# Boost_5V.net
KiCad netlist of a schematic drawn in Altium Designer
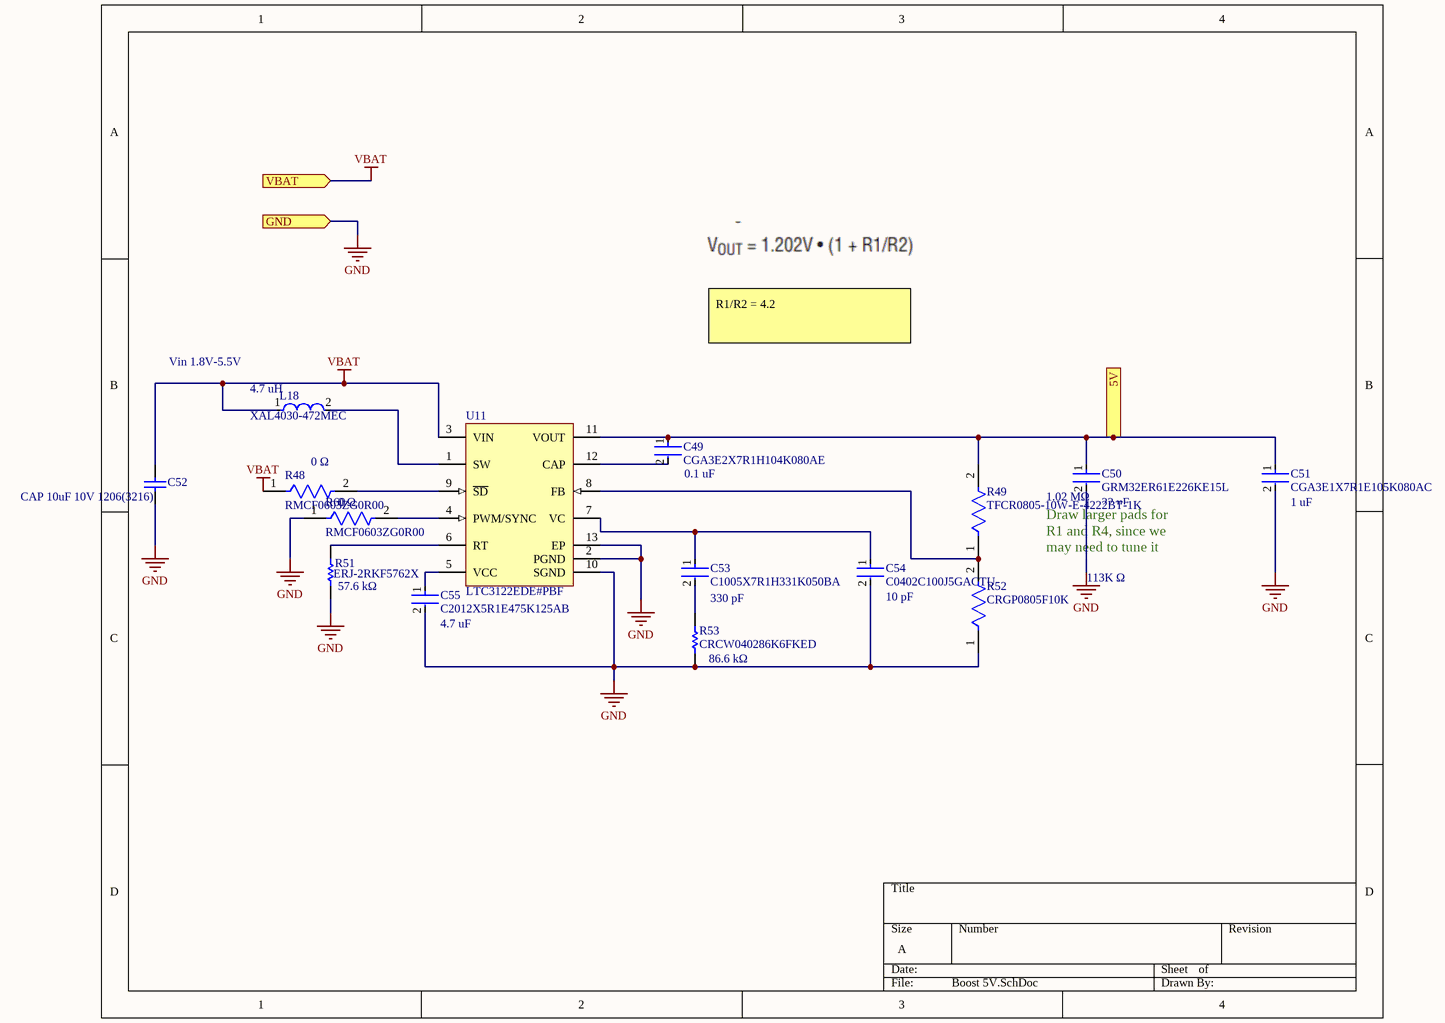
[diagram p0: Boost 5V.SchDoc]

(export (version "E")
  (design (tool "Eeschema 10.0.6"))
  (components
    (comp (ref "C49")
      (value "CGA3E2X7R1H104K080AE")
      (footprint "FP-CGA3E-0_3-0_1-IPC_A")
      (description "Cap Ceramic 100nF 50V X7R 10% Pad SMD 0603 +125°C Automotive T/R")
      (fields (field (name "TOLERANCE") "10%"))
      (libsource (lib "Altium Content Vault") (part "b4654b650e69147ec39a6b967a45e02"))
    )
    (comp (ref "C50")
      (value "GRM32ER61E226KE15L")
      (footprint "FP-GRM32-MFG")
      (description "CAP CER 22UF 25V X5R 1210")
      (fields
        (field (name "TOLERANCE") "10%")
        (field (name "MANUFACTURER") "Murata Electronics North America")
      )
      (libsource (lib "Altium Content Vault") (part "11868f565c42a9108669ba33697ecf6"))
    )
    (comp (ref "C51")
      (value "CGA3E1X7R1E105K080AC")
      (footprint "FP-CGA3E-0_3-0_1-IPC_A")
      (description "Cap Ceramic 1uF 25V X7R 10% Pad SMD 0603 +125°C Automotive T/R")
      (fields (field (name "VOLTAGE") "25V") (field (name "TOLERANCE") "10%"))
      (libsource (lib "Altium Content Vault") (part "b4654b650e69147ec39a6b967a45e02"))
    )
    (comp (ref "C52")
      (value "CAP 10uF 10V 1206(3216)")
      (footprint "CAPC1206(3216)190_L")
      (description "CAP 10uF 10V ±10% 1206 (3216 Metric) Thickness 1.9mm SMD")
      (fields (field (name "TOLERANCE") "Â±10%"))
      (libsource (lib "Altium Content Vault") (part "CAP"))
    )
    (comp (ref "C53")
      (value "C1005X7R1H331K050BA")
      (footprint "FP-C1005-050-0_05-IPC_B")
      (description "Multilayer Ceramic Capacitors 330pF ±10% 50V X7R SMD 0402")
      (fields (field (name "TOLERANCE") "10%"))
      (libsource (lib "Altium Content Vault") (part "b4654b650e69147ec39a6b967a45e02"))
    )
    (comp (ref "C54")
      (value "C0402C100J5GACTU")
      (footprint "FP-C0402-BB-MFG")
      (fields
        (field (name "MANUFACTURER") "Kemet")
        (field (name "OCTOPART") "https://octopart.com/c0402c100j5gactu-kemet-108448")
        (field (name "TOLERANCE") "0.05")
      )
      (libsource (lib "Altium Content Vault") (part "b4654b650e69147ec39a6b967a45e02"))
    )
    (comp (ref "C55")
      (value "C2012X5R1E475K125AB")
      (footprint "FP-C2012-125-0_2-MFG")
      (description "Multilayer Ceramic Capacitors 4.7μF ±10% 25V X5R SMD 0805")
      (fields (field (name "VOLTAGE") "25V") (field (name "TOLERANCE") "10%"))
      (libsource (lib "Altium Content Vault") (part "b4654b650e69147ec39a6b967a45e02"))
    )
    (comp (ref "L18")
      (value "XAL4030-472MEC")
      (footprint "FP-XAL4030-472MEC-MFG")
      (description "Power Inductor (SMD), 4.7 µH, 5.1 A, Shielded, 4.5 A, XAL40xx Series, 4mm x 4mm x 3.1mm")
      (fields (field (name "TOLERANCE") "20%"))
      (libsource (lib "Altium Content Vault") (part "725321dda6339637d4d059423bc1c3c"))
    )
    (comp (ref "R48")
      (value "RMCF0603ZG0R00")
      (footprint "FP-RMCF0603-IPC_B")
      (description "0Ω ±0 0.1W 0603 Thick Film Chip Resistor AEC-Q200 compliant")
      (libsource (lib "Altium Content Vault") (part "1029c3af85768c4190bb7ad29bc67b5"))
    )
    (comp (ref "R49")
      (value "TFCR0805-10W-E-4222BT-1K")
      (footprint "FP-TFCR0805-IPC_A")
      (description "RES Thin Film,  42.2kΩ, 0.1%, 0.1W, 25ppm/°C, 0805")
      (libsource (lib "Altium Content Vault") (part "1029c3af85768c4190bb7ad29bc67b5"))
    )
    (comp (ref "R51")
      (value "ERJ-2RKF5762X")
      (footprint "RESC1005X40X25NL05T05")
      (fields (field (name "MANUFACTURER") "Panasonic"))
      (libsource (lib "Altium Content Vault") (part "RES"))
    )
    (comp (ref "R52")
      (value "CRGP0805F10K")
      (footprint "FP-CRGP0805-IPC_C")
      (description "CRGP 0805 10K 1%")
      (fields
        (field (name "MANUFACTURER") "TE")
        (field (name "OCTOPART") "https://octopart.com/crgp0805f10k-te+connectivity-91018782")
      )
      (libsource (lib "Altium Content Vault") (part "1029c3af85768c4190bb7ad29bc67b5"))
    )
    (comp (ref "R53")
      (value "CRCW040286K6FKED")
      (footprint "RESC1005X40X25NL05T05")
      (fields (field (name "MANUFACTURER") "Vishay Dale"))
      (libsource (lib "Altium Content Vault") (part "RES"))
    )
    (comp (ref "R60")
      (value "RMCF0603ZG0R00")
      (footprint "FP-RMCF0603-IPC_B")
      (description "0Ω ±0 0.1W 0603 Thick Film Chip Resistor AEC-Q200 compliant")
      (libsource (lib "Altium Content Vault") (part "1029c3af85768c4190bb7ad29bc67b5"))
    )
    (comp (ref "U11")
      (value "LTC3122EDE#PBF")
      (footprint "LT-DE-UE-12_V")
      (fields (field (name "MANUFACTURER") "Linear Technology"))
      (libsource (lib "Altium Content Vault") (part "LT-LTC3122-X-12"))
    )
  )
  (nets
    (net (code "1") (name "/5V") (class "Default")
      (node (ref "C49") (pin "1") (pinfunction "1_1") (pintype "passive"))
      (node (ref "C50") (pin "1") (pinfunction "1_1") (pintype "passive"))
      (node (ref "C51") (pin "1") (pinfunction "1_1") (pintype "passive"))
      (node (ref "R49") (pin "2") (pinfunction "2_2") (pintype "passive"))
      (node (ref "U11") (pin "11") (pinfunction "VOUT_11") (pintype "power_in"))
    )
    (net (code "2") (name "GND") (class "Default")
      (node (ref "C50") (pin "2") (pinfunction "2_2") (pintype "passive"))
      (node (ref "C51") (pin "2") (pinfunction "2_2") (pintype "passive"))
      (node (ref "C52") (pin "1") (pinfunction "1_1") (pintype "passive"))
      (node (ref "C54") (pin "2") (pinfunction "2_2") (pintype "passive"))
      (node (ref "C55") (pin "2") (pinfunction "2_2") (pintype "passive"))
      (node (ref "R51") (pin "1") (pinfunction "1_1") (pintype "passive"))
      (node (ref "R52") (pin "1") (pinfunction "1_1") (pintype "passive"))
      (node (ref "R53") (pin "1") (pinfunction "1_1") (pintype "passive"))
      (node (ref "R60") (pin "1") (pinfunction "1_1") (pintype "passive"))
      (node (ref "U11") (pin "10") (pinfunction "SGND_10") (pintype "power_in"))
      (node (ref "U11") (pin "13") (pinfunction "EP_13") (pintype "power_in"))
      (node (ref "U11") (pin "2") (pinfunction "PGND_2") (pintype "power_in"))
    )
    (net (code "3") (name "Net-(C53-Pad2)") (class "Default")
      (node (ref "C53") (pin "2") (pinfunction "2_2") (pintype "passive"))
      (node (ref "R53") (pin "2") (pinfunction "2_2") (pintype "passive"))
    )
    (net (code "4") (name "Net-(U11-CAP)") (class "Default")
      (node (ref "C49") (pin "2") (pinfunction "2_2") (pintype "passive"))
      (node (ref "U11") (pin "12") (pinfunction "CAP_12") (pintype "passive"))
    )
    (net (code "5") (name "Net-(U11-FB)") (class "Default")
      (node (ref "R49") (pin "1") (pinfunction "1_1") (pintype "passive"))
      (node (ref "R52") (pin "2") (pinfunction "2_2") (pintype "passive"))
      (node (ref "U11") (pin "8") (pinfunction "FB_8") (pintype "input"))
    )
    (net (code "6") (name "Net-(U11-PWM{slash}SYNC)") (class "Default")
      (node (ref "R60") (pin "2") (pinfunction "2_2") (pintype "passive"))
      (node (ref "U11") (pin "4") (pinfunction "PWM/SYNC_4") (pintype "input"))
    )
    (net (code "7") (name "Net-(U11-RT)") (class "Default")
      (node (ref "R51") (pin "2") (pinfunction "2_2") (pintype "passive"))
      (node (ref "U11") (pin "6") (pinfunction "RT_6") (pintype "passive"))
    )
    (net (code "8") (name "Net-(U11-SW)") (class "Default")
      (node (ref "L18") (pin "2") (pinfunction "2_2") (pintype "passive"))
      (node (ref "U11") (pin "1") (pinfunction "SW_1") (pintype "passive"))
    )
    (net (code "9") (name "Net-(U11-VC)") (class "Default")
      (node (ref "C53") (pin "1") (pinfunction "1_1") (pintype "passive"))
      (node (ref "C54") (pin "1") (pinfunction "1_1") (pintype "passive"))
      (node (ref "U11") (pin "7") (pinfunction "VC_7") (pintype "passive"))
    )
    (net (code "10") (name "Net-(U11-VCC)") (class "Default")
      (node (ref "C55") (pin "1") (pinfunction "1_1") (pintype "passive"))
      (node (ref "U11") (pin "5") (pinfunction "VCC_5") (pintype "power_in"))
    )
    (net (code "11") (name "Net-(U11-~{SD})") (class "Default")
      (node (ref "R48") (pin "2") (pinfunction "2_2") (pintype "passive"))
      (node (ref "U11") (pin "9") (pinfunction "~{SD}_9") (pintype "input"))
    )
    (net (code "12") (name "VBAT") (class "Default")
      (node (ref "C52") (pin "2") (pinfunction "2_2") (pintype "passive"))
      (node (ref "L18") (pin "1") (pinfunction "1_1") (pintype "passive"))
      (node (ref "R48") (pin "1") (pinfunction "1_1") (pintype "passive"))
      (node (ref "U11") (pin "3") (pinfunction "VIN_3") (pintype "power_in"))
    )
  )
)
